# G-103P-P-20190703_wifi.net
KiCad netlist of a schematic drawn in Altium Designer
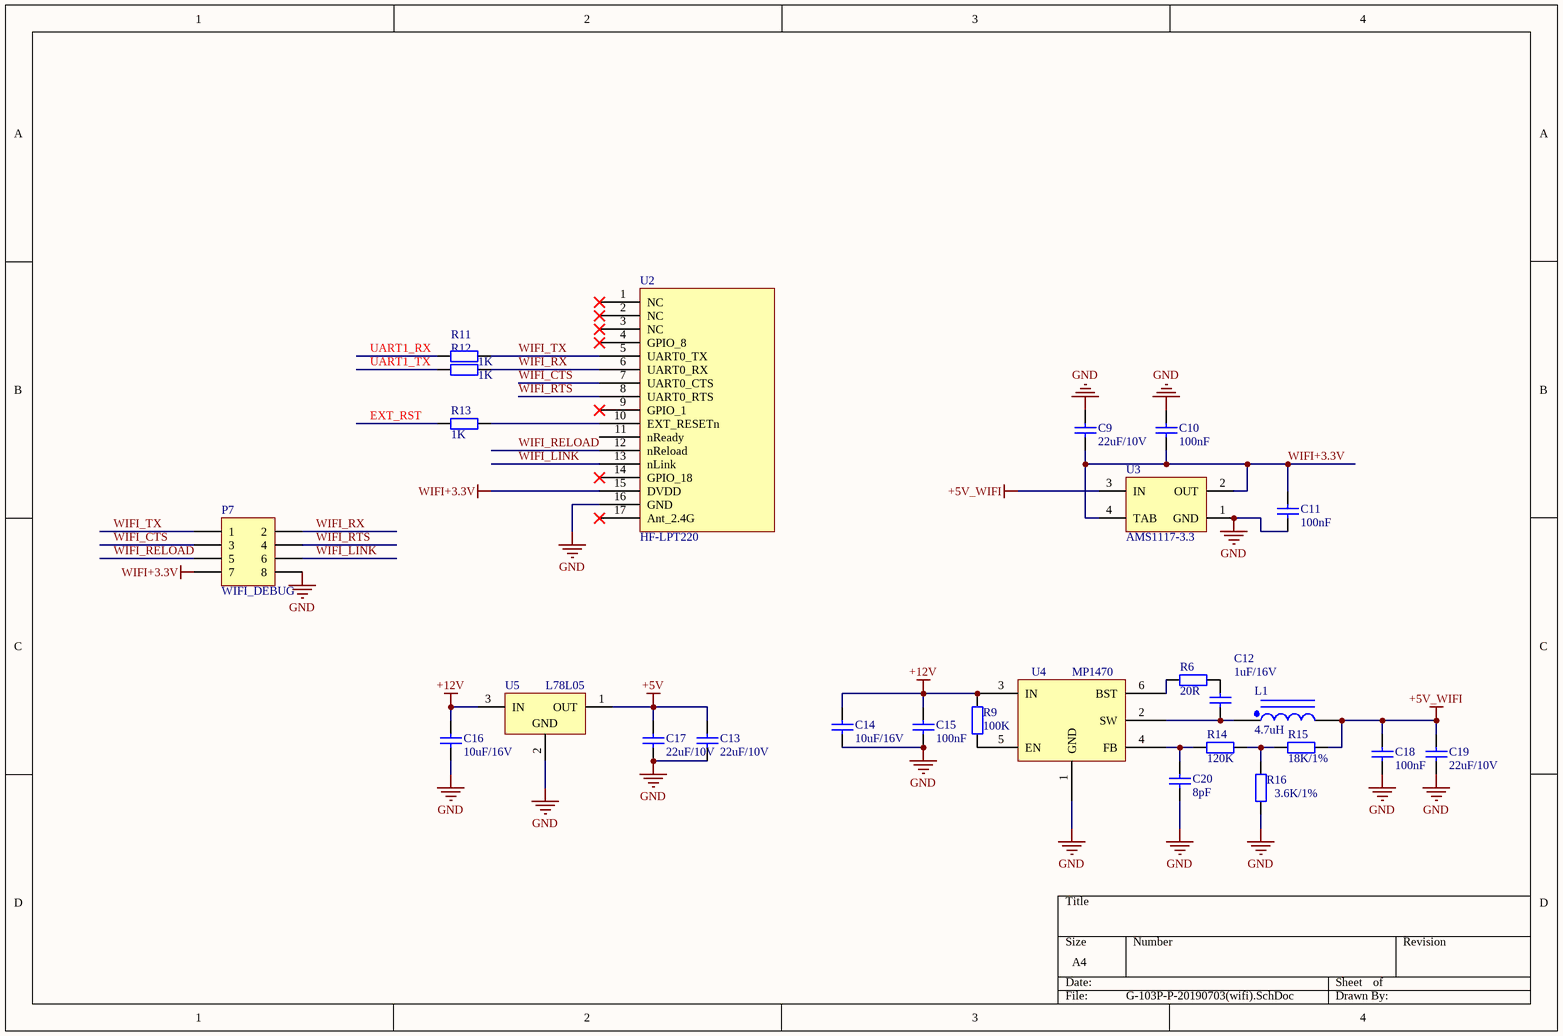
[diagram p0: G-103P-P-20190703(wifi).SchDoc]

(export (version "E")
  (design (tool "Eeschema 10.0.6"))
  (components
    (comp (ref "C9")
      (value "22uF/10V")
      (footprint "SMD-0603")
      (description "Capacitor")
      (libsource (lib "Miscellaneous Devices") (part "Cap"))
    )
    (comp (ref "C10")
      (value "100nF")
      (footprint "SMD-0603")
      (description "Capacitor")
      (fields (field (name "PUBLISHER") "Altium Limited"))
      (libsource (lib "Miscellaneous Devices") (part "Cap"))
    )
    (comp (ref "C11")
      (value "100nF")
      (footprint "SMD-0603")
      (description "Capacitor")
      (fields (field (name "PUBLISHER") "Altium Limited"))
      (libsource (lib "Miscellaneous Devices") (part "Cap"))
    )
    (comp (ref "C12")
      (value "1uF/16V")
      (footprint "SMD-0603")
      (description "贴片电容")
      (libsource (lib "RT5350M1") (part "SMDCAP"))
    )
    (comp (ref "C13")
      (value "22uF/10V")
      (footprint "SMD-0603")
      (description "贴片电容")
      (libsource (lib "RT5350M1") (part "SMDCAP"))
    )
    (comp (ref "C14")
      (value "10uF/16V")
      (footprint "SMD-0603")
      (description "Capacitor")
      (fields (field (name "PUBLISHER") "Altium Limited"))
      (libsource (lib "Miscellaneous Devices") (part "Cap"))
    )
    (comp (ref "C15")
      (value "100nF")
      (footprint "SMD-0603")
      (description "贴片电容")
      (libsource (lib "RT5350M1") (part "SMDCAP"))
    )
    (comp (ref "C16")
      (value "10uF/16V")
      (footprint "SMD-0603")
      (description "Capacitor")
      (fields (field (name "PUBLISHER") "Altium Limited"))
      (libsource (lib "Miscellaneous Devices") (part "Cap"))
    )
    (comp (ref "C17")
      (value "22uF/10V")
      (footprint "SMD-0603")
      (description "贴片电容")
      (libsource (lib "RT5350M1") (part "SMDCAP"))
    )
    (comp (ref "C18")
      (value "100nF")
      (footprint "SMD-0603")
      (description "贴片电容")
      (libsource (lib "RT5350M1") (part "SMDCAP"))
    )
    (comp (ref "C19")
      (value "22uF/10V")
      (footprint "SMD-0603")
      (description "贴片电容")
      (libsource (lib "RT5350M1") (part "SMDCAP"))
    )
    (comp (ref "C20")
      (value "8pF")
      (footprint "SMD-0603")
      (description "贴片电容")
      (libsource (lib "RT5350M1") (part "SMDCAP"))
    )
    (comp (ref "L1")
      (value "4.7uH")
      (footprint "NR3010")
      (description "贴片电感")
      (libsource (lib "Miscellaneous Devices") (part "Inductor Iron Dot"))
    )
    (comp (ref "P7")
      (value "WIFI_DEBUG")
      (footprint "HDR2X4")
      (description "Header, 4-Pin, Dual row")
      (fields (field (name "PUBLISHER") "Altium Limited"))
      (libsource (lib "Miscellaneous Connectors") (part "Header 4X2"))
    )
    (comp (ref "R6")
      (value "20R")
      (footprint "SMD-0603")
      (description "贴片电阻")
      (libsource (lib "") (part "SMDRES_1"))
    )
    (comp (ref "R9")
      (value "100K")
      (footprint "SMD-0603")
      (description "贴片电阻")
      (libsource (lib "RT5350M1") (part "SMDRES"))
    )
    (comp (ref "R11")
      (value "1K")
      (footprint "SMD-0603")
      (description "Resistor")
      (fields (field (name "PUBLISHER") "Altium Limited"))
      (libsource (lib "Miscellaneous Devices") (part "Res2"))
    )
    (comp (ref "R12")
      (value "1K")
      (footprint "SMD-0603")
      (description "Resistor")
      (fields (field (name "PUBLISHER") "Altium Limited"))
      (libsource (lib "Miscellaneous Devices") (part "Res2"))
    )
    (comp (ref "R13")
      (value "1K")
      (footprint "SMD-0603")
      (description "Resistor")
      (fields (field (name "PUBLISHER") "Altium Limited"))
      (libsource (lib "Miscellaneous Devices") (part "Res2"))
    )
    (comp (ref "R14")
      (value "120K")
      (footprint "SMD-0603")
      (description "贴片电阻")
      (libsource (lib "") (part "SMDRES_1"))
    )
    (comp (ref "R15")
      (value "18K/1%")
      (footprint "SMD-0603")
      (description "贴片电阻")
      (libsource (lib "RT5350M1") (part "SMDRES"))
    )
    (comp (ref "R16")
      (value "3.6K/1%")
      (footprint "SMD-0603")
      (description "贴片电阻")
      (libsource (lib "") (part "SMDRES_2"))
    )
    (comp (ref "U2") (value "HF-LPT220") (footprint "HF-LPT220") (libsource (lib "MZN01") (part "HF-LPT220")))
    (comp (ref "U3")
      (value "AMS1117-3.3")
      (footprint "SOT223")
      (description "800mA Low-Dropout Linear Regulator")
      (fields
        (field (name "PARTNUMBER") "LM1117IMP-3.3")
        (field (name "MANUFACTURER") "National Semiconductor")
        (field (name "PUBLISHER") "Altium Limited")
      )
      (libsource (lib "NSC LDO") (part "LM1117IMP-3.3"))
    )
    (comp (ref "U4")
      (value "MP1470")
      (footprint "SOT23-6A")
      (description "DCDC降压芯片")
      (libsource (lib "AQ801") (part "MP1470"))
    )
    (comp (ref "U5")
      (value "L78L05")
      (footprint "SOT89")
      (description "Positive Voltage Regulator")
      (fields (field (name "PUBLISHER") "Altium Limited"))
      (libsource (lib "ST Power Mgt Voltage Regulator") (part "L78L05CZ"))
    )
  )
  (nets
    (net (code "1") (name "+5V") (class "Default")
      (node (ref "C13") (pin "1") (pinfunction "1_1") (pintype "passive"))
      (node (ref "C17") (pin "1") (pinfunction "1_1") (pintype "passive"))
      (node (ref "U5") (pin "1") (pinfunction "OUT_1") (pintype "power_in"))
    )
    (net (code "2") (name "+5V_WIFI") (class "Default")
      (node (ref "C18") (pin "1") (pinfunction "1_1") (pintype "passive"))
      (node (ref "C19") (pin "1") (pinfunction "1_1") (pintype "passive"))
      (node (ref "L1") (pin "2") (pinfunction "2_2") (pintype "passive"))
      (node (ref "R15") (pin "2") (pinfunction "2_2") (pintype "passive"))
      (node (ref "U3") (pin "3") (pinfunction "IN_3") (pintype "power_in"))
    )
    (net (code "3") (name "+12V") (class "Default")
      (node (ref "C14") (pin "1") (pinfunction "1_1") (pintype "passive"))
      (node (ref "C15") (pin "1") (pinfunction "1_1") (pintype "passive"))
      (node (ref "C16") (pin "1") (pinfunction "1_1") (pintype "passive"))
      (node (ref "R9") (pin "2") (pinfunction "2_2") (pintype "passive"))
      (node (ref "U4") (pin "3") (pinfunction "IN_3") (pintype "passive"))
      (node (ref "U5") (pin "3") (pinfunction "IN_3") (pintype "power_in"))
    )
    (net (code "4") (name "/EXT_RST") (class "Default")
      (node (ref "R13") (pin "2") (pinfunction "2_2") (pintype "passive"))
    )
    (net (code "5") (name "/UART1_RX") (class "Default")
      (node (ref "R11") (pin "2") (pinfunction "2_2") (pintype "passive"))
    )
    (net (code "6") (name "/UART1_TX") (class "Default")
      (node (ref "R12") (pin "2") (pinfunction "2_2") (pintype "passive"))
    )
    (net (code "7") (name "/WIFI_CTS") (class "Default")
      (node (ref "P7") (pin "3") (pinfunction "3_3") (pintype "passive"))
      (node (ref "U2") (pin "7") (pinfunction "UART0_CTS_7") (pintype "passive"))
    )
    (net (code "8") (name "/WIFI_LINK") (class "Default")
      (node (ref "P7") (pin "6") (pinfunction "6_6") (pintype "passive"))
      (node (ref "U2") (pin "13") (pinfunction "nLink_13") (pintype "passive"))
    )
    (net (code "9") (name "/WIFI_RELOAD") (class "Default")
      (node (ref "P7") (pin "5") (pinfunction "5_5") (pintype "passive"))
      (node (ref "U2") (pin "12") (pinfunction "nReload_12") (pintype "passive"))
    )
    (net (code "10") (name "/WIFI_RTS") (class "Default")
      (node (ref "P7") (pin "4") (pinfunction "4_4") (pintype "passive"))
      (node (ref "U2") (pin "8") (pinfunction "UART0_RTS_8") (pintype "passive"))
    )
    (net (code "11") (name "/WIFI_RX") (class "Default")
      (node (ref "P7") (pin "2") (pinfunction "2_2") (pintype "passive"))
      (node (ref "R12") (pin "1") (pinfunction "1_1") (pintype "passive"))
      (node (ref "U2") (pin "6") (pinfunction "UART0_RX_6") (pintype "passive"))
    )
    (net (code "12") (name "/WIFI_TX") (class "Default")
      (node (ref "P7") (pin "1") (pinfunction "1_1") (pintype "passive"))
      (node (ref "R11") (pin "1") (pinfunction "1_1") (pintype "passive"))
      (node (ref "U2") (pin "5") (pinfunction "UART0_TX_5") (pintype "passive"))
    )
    (net (code "13") (name "GND") (class "Default")
      (node (ref "C10") (pin "2") (pinfunction "2_2") (pintype "passive"))
      (node (ref "C11") (pin "2") (pinfunction "2_2") (pintype "passive"))
      (node (ref "C13") (pin "2") (pinfunction "2_2") (pintype "passive"))
      (node (ref "C14") (pin "2") (pinfunction "2_2") (pintype "passive"))
      (node (ref "C15") (pin "2") (pinfunction "2_2") (pintype "passive"))
      (node (ref "C16") (pin "2") (pinfunction "2_2") (pintype "passive"))
      (node (ref "C17") (pin "2") (pinfunction "2_2") (pintype "passive"))
      (node (ref "C18") (pin "2") (pinfunction "2_2") (pintype "passive"))
      (node (ref "C19") (pin "2") (pinfunction "2_2") (pintype "passive"))
      (node (ref "C20") (pin "1") (pinfunction "1_1") (pintype "passive"))
      (node (ref "C9") (pin "1") (pinfunction "1_1") (pintype "passive"))
      (node (ref "P7") (pin "8") (pinfunction "8_8") (pintype "passive"))
      (node (ref "R16") (pin "1") (pinfunction "1_1") (pintype "passive"))
      (node (ref "U2") (pin "16") (pinfunction "GND_16") (pintype "passive"))
      (node (ref "U3") (pin "1") (pinfunction "GND_1") (pintype "power_in"))
      (node (ref "U4") (pin "1") (pinfunction "GND_1") (pintype "passive"))
      (node (ref "U5") (pin "2") (pinfunction "GND_2") (pintype "power_in"))
    )
    (net (code "14") (name "Net-(C12-Pad2)") (class "Default")
      (node (ref "C12") (pin "2") (pinfunction "2_2") (pintype "passive"))
      (node (ref "R6") (pin "1") (pinfunction "1_1") (pintype "passive"))
    )
    (net (code "15") (name "Net-(R14-Pad1)") (class "Default")
      (node (ref "R14") (pin "1") (pinfunction "1_1") (pintype "passive"))
      (node (ref "R15") (pin "1") (pinfunction "1_1") (pintype "passive"))
      (node (ref "R16") (pin "2") (pinfunction "2_2") (pintype "passive"))
    )
    (net (code "16") (name "Net-(U2-EXT_RESETn)") (class "Default")
      (node (ref "R13") (pin "1") (pinfunction "1_1") (pintype "passive"))
      (node (ref "U2") (pin "10") (pinfunction "EXT_RESETn_10") (pintype "passive"))
    )
    (net (code "17") (name "Net-(U4-BST)") (class "Default")
      (node (ref "R6") (pin "2") (pinfunction "2_2") (pintype "passive"))
      (node (ref "U4") (pin "6") (pinfunction "BST_6") (pintype "passive"))
    )
    (net (code "18") (name "Net-(U4-EN)") (class "Default")
      (node (ref "R9") (pin "1") (pinfunction "1_1") (pintype "passive"))
      (node (ref "U4") (pin "5") (pinfunction "EN_5") (pintype "passive"))
    )
    (net (code "19") (name "Net-(U4-FB)") (class "Default")
      (node (ref "C20") (pin "2") (pinfunction "2_2") (pintype "passive"))
      (node (ref "R14") (pin "2") (pinfunction "2_2") (pintype "passive"))
      (node (ref "U4") (pin "4") (pinfunction "FB_4") (pintype "passive"))
    )
    (net (code "20") (name "Net-(U4-SW)") (class "Default")
      (node (ref "C12") (pin "1") (pinfunction "1_1") (pintype "passive"))
      (node (ref "L1") (pin "1") (pinfunction "1_1") (pintype "passive"))
      (node (ref "U4") (pin "2") (pinfunction "SW_2") (pintype "passive"))
    )
    (net (code "21") (name "WIFI+3.3V") (class "Default")
      (node (ref "C10") (pin "1") (pinfunction "1_1") (pintype "passive"))
      (node (ref "C11") (pin "1") (pinfunction "1_1") (pintype "passive"))
      (node (ref "C9") (pin "2") (pinfunction "2_2") (pintype "passive"))
      (node (ref "P7") (pin "7") (pinfunction "7_7") (pintype "passive"))
      (node (ref "U2") (pin "15") (pinfunction "DVDD_15") (pintype "passive"))
      (node (ref "U3") (pin "2") (pinfunction "OUT_2") (pintype "power_in"))
      (node (ref "U3") (pin "4") (pinfunction "TAB_4") (pintype "power_in"))
    )
    (net (code "22") (name "unconnected-(U2-Ant_2.4G-Pad17)") (class "Default")
      (node (ref "U2") (pin "17") (pinfunction "Ant_2.4G_17") (pintype "passive+no_connect"))
    )
    (net (code "23") (name "unconnected-(U2-GPIO_1-Pad9)") (class "Default")
      (node (ref "U2") (pin "9") (pinfunction "GPIO_1_9") (pintype "passive+no_connect"))
    )
    (net (code "24") (name "unconnected-(U2-GPIO_8-Pad4)") (class "Default")
      (node (ref "U2") (pin "4") (pinfunction "GPIO_8_4") (pintype "passive+no_connect"))
    )
    (net (code "25") (name "unconnected-(U2-GPIO_18-Pad14)") (class "Default")
      (node (ref "U2") (pin "14") (pinfunction "GPIO_18_14") (pintype "passive+no_connect"))
    )
    (net (code "26") (name "unconnected-(U2-NC-Pad1)") (class "Default")
      (node (ref "U2") (pin "1") (pinfunction "NC_1") (pintype "passive+no_connect"))
    )
    (net (code "27") (name "unconnected-(U2-NC-Pad2)") (class "Default")
      (node (ref "U2") (pin "2") (pinfunction "NC_2") (pintype "passive+no_connect"))
    )
    (net (code "28") (name "unconnected-(U2-NC-Pad3)") (class "Default")
      (node (ref "U2") (pin "3") (pinfunction "NC_3") (pintype "passive+no_connect"))
    )
    (net (code "29") (name "unconnected-(U2-nReady-Pad11)") (class "Default")
      (node (ref "U2") (pin "11") (pinfunction "nReady_11") (pintype "passive"))
    )
  )
)
